# OpenPack_BATMOD_V1p0_PWR.net
KiCad netlist of a schematic drawn in Altium Designer
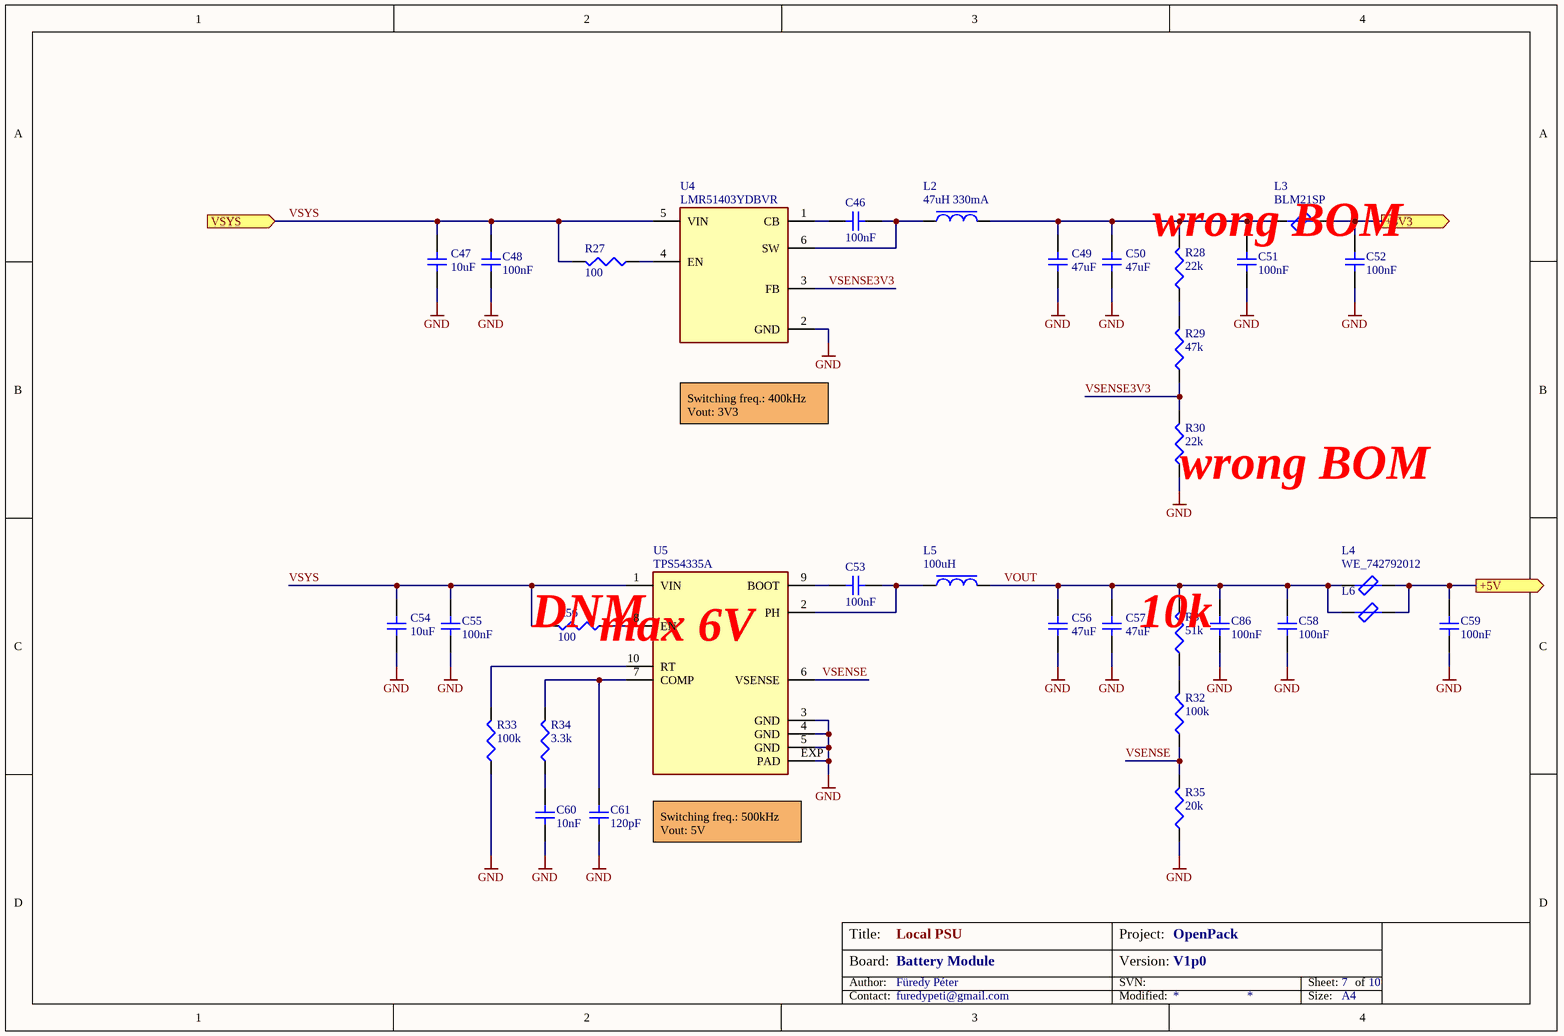
[diagram p0: OpenPack_BATMOD_V1p0_PWR.SchDoc]

(export (version "E")
  (design (tool "Eeschema 10.0.6"))
  (components
    (comp (ref "C46")
      (value "100nF")
      (footprint "CAP_0603")
      (description "MLCC capacitor")
      (libsource (lib "SCHLIB") (part "NP-CAPACITOR"))
    )
    (comp (ref "C47")
      (value "10uF")
      (footprint "CAP_1210")
      (description "UMK325BJ106KM-P")
      (fields (field (name "PART NUMBER") "810-CGA6P1X7R1N106K2"))
      (libsource (lib "SCHLIB") (part "NP-CAPACITOR"))
    )
    (comp (ref "C48")
      (value "100nF")
      (footprint "CAP_0603")
      (description "MLCC capacitor")
      (libsource (lib "SCHLIB") (part "NP-CAPACITOR"))
    )
    (comp (ref "C49")
      (value "47uF")
      (footprint "CAP_1210")
      (description "Np-Cap")
      (fields (field (name "PART NUMBER") "80-C1210C476M4P"))
      (libsource (lib "SCHLIB") (part "NP-CAPACITOR"))
    )
    (comp (ref "C50")
      (value "47uF")
      (footprint "CAP_1210")
      (description "Np-Cap")
      (fields (field (name "PART NUMBER") "80-C1210C476M4P"))
      (libsource (lib "SCHLIB") (part "NP-CAPACITOR"))
    )
    (comp (ref "C51")
      (value "100nF")
      (footprint "CAP_0603")
      (description "MLCC capacitor")
      (libsource (lib "SCHLIB") (part "NP-CAPACITOR"))
    )
    (comp (ref "C52")
      (value "100nF")
      (footprint "CAP_0603")
      (description "MLCC capacitor")
      (libsource (lib "SCHLIB") (part "NP-CAPACITOR"))
    )
    (comp (ref "C53")
      (value "100nF")
      (footprint "CAP_0603")
      (description "MLCC capacitor")
      (libsource (lib "SCHLIB") (part "NP-CAPACITOR"))
    )
    (comp (ref "C54")
      (value "10uF")
      (footprint "CAP_1210")
      (description "UMK325BJ106KM-P")
      (fields (field (name "PART NUMBER") "810-CGA6P1X7R1N106K2"))
      (libsource (lib "SCHLIB") (part "NP-CAPACITOR"))
    )
    (comp (ref "C55")
      (value "100nF")
      (footprint "CAP_0603")
      (description "MLCC capacitor")
      (libsource (lib "SCHLIB") (part "NP-CAPACITOR"))
    )
    (comp (ref "C56")
      (value "47uF")
      (footprint "CAP_1210")
      (description "Np-Cap")
      (fields (field (name "PART NUMBER") "80-C1210C476M4P"))
      (libsource (lib "SCHLIB") (part "NP-CAPACITOR"))
    )
    (comp (ref "C57")
      (value "47uF")
      (footprint "CAP_1210")
      (description "Np-Cap")
      (fields (field (name "PART NUMBER") "80-C1210C476M4P"))
      (libsource (lib "SCHLIB") (part "NP-CAPACITOR"))
    )
    (comp (ref "C58")
      (value "100nF")
      (footprint "CAP_0603")
      (description "MLCC capacitor")
      (libsource (lib "SCHLIB") (part "NP-CAPACITOR"))
    )
    (comp (ref "C59")
      (value "100nF")
      (footprint "CAP_0603")
      (description "MLCC capacitor")
      (libsource (lib "SCHLIB") (part "NP-CAPACITOR"))
    )
    (comp (ref "C60")
      (value "10nF")
      (footprint "CAP_0603")
      (description "MLCC capacitor")
      (libsource (lib "SCHLIB") (part "NP-CAPACITOR"))
    )
    (comp (ref "C61")
      (value "120pF")
      (footprint "CAP_0603")
      (description "MLCC capacitor")
      (libsource (lib "SCHLIB") (part "NP-CAPACITOR"))
    )
    (comp (ref "C86")
      (value "100nF")
      (footprint "CAP_0603")
      (description "MLCC capacitor")
      (libsource (lib "SCHLIB") (part "NP-CAPACITOR"))
    )
    (comp (ref "L2")
      (value "47uH 330mA")
      (footprint "IND_1210")
      (description "Power inductor")
      (fields (field (name "PART NUMBER") "81-LQH32PN470MN0L"))
      (libsource (lib "SCHLIB") (part "Inductance - 47uH"))
    )
    (comp (ref "L3")
      (value "BLM21SP")
      (footprint "IND-0805")
      (description "Chip Ferrite Bead, 1000R @100MHz, 1.6A")
      (fields (field (name "PART NUMBER") "81-BLM21SP102SN1D"))
      (libsource (lib "SCHLIB") (part "BLM21SP102SN1D"))
    )
    (comp (ref "L4")
      (value "WE_742792012")
      (footprint "IND-0805")
      (description "Chip Ferrite Bead, 33R @100MHz, 4A")
      (fields (field (name "PART NUMBER") "710-742792012"))
      (libsource (lib "SCHLIB") (part "WE_742792012"))
    )
    (comp (ref "L5")
      (value "100uH")
      (footprint "IND_2")
      (description "Ferrit core coil, 22uH 2.85A, 75mR")
      (fields (field (name "PART NUMBER") "994-MSS1038T-223MLC"))
      (libsource (lib "SCHLIB") (part "Inductance - 22uH"))
    )
    (comp (ref "L6")
      (value "WE_742792012")
      (footprint "IND-0805")
      (description "Chip Ferrite Bead, 33R @100MHz, 4A")
      (fields (field (name "PART NUMBER") "710-742792012"))
      (libsource (lib "SCHLIB") (part "WE_742792012"))
    )
    (comp (ref "R27")
      (value "100")
      (footprint "RES-0603")
      (description "Metal Film Resistor")
      (libsource (lib "SCHLIB") (part "RESISTOR"))
    )
    (comp (ref "R28")
      (value "22k")
      (footprint "RES-0603")
      (description "Metal Film Resistor")
      (libsource (lib "SCHLIB") (part "RESISTOR"))
    )
    (comp (ref "R29")
      (value "47k")
      (footprint "RES-0603")
      (description "Metal Film Resistor")
      (libsource (lib "SCHLIB") (part "RESISTOR"))
    )
    (comp (ref "R30")
      (value "22k")
      (footprint "RES-0603")
      (description "Metal Film Resistor")
      (libsource (lib "SCHLIB") (part "RESISTOR"))
    )
    (comp (ref "R31")
      (value "51k")
      (footprint "RES-0603")
      (description "Metal Film Resistor")
      (libsource (lib "SCHLIB") (part "RESISTOR"))
    )
    (comp (ref "R32")
      (value "100k")
      (footprint "RES-0603")
      (description "Metal Film Resistor")
      (libsource (lib "SCHLIB") (part "RESISTOR"))
    )
    (comp (ref "R33")
      (value "100k")
      (footprint "RES-0603")
      (description "Metal Film Resistor")
      (libsource (lib "SCHLIB") (part "RESISTOR"))
    )
    (comp (ref "R34")
      (value "3.3k")
      (footprint "RES-0603")
      (description "Metal Film Resistor")
      (libsource (lib "SCHLIB") (part "RESISTOR"))
    )
    (comp (ref "R35")
      (value "20k")
      (footprint "RES-0603")
      (description "Metal Film Resistor")
      (libsource (lib "SCHLIB") (part "RESISTOR"))
    )
    (comp (ref "R56")
      (value "100")
      (footprint "RES-0603")
      (description "Metal Film Resistor")
      (libsource (lib "SCHLIB") (part "RESISTOR"))
    )
    (comp (ref "U4")
      (value "LMR51403YDBVR")
      (footprint "SOT-23-6")
      (description "Switching Voltage Regulators 4.5V-to-42V 0.3A syn chronous buck conve")
      (fields (field (name "PART NUMBER") "595-LMR51403YDBVR"))
      (libsource (lib "SCHLIB") (part "LMR51403YDBVR"))
    )
    (comp (ref "U5")
      (value "TPS54335A")
      (footprint "VSON-10")
      (description "Switching Voltage Regulators 4.5Vto28VInp 3A Sync Step-Down Converter A 595-TPS54335ADRCT")
      (fields (field (name "PART NUMBER") "595-TPS54335ADRCR"))
      (libsource (lib "SCHLIB") (part "TPS54335A"))
    )
  )
  (nets
    (net (code "1") (name "/+3V3") (class "Default")
      (node (ref "C52") (pin "1") (pinfunction "1_1") (pintype "passive"))
      (node (ref "L3") (pin "2") (pinfunction "2_2") (pintype "passive"))
    )
    (net (code "2") (name "/+5V") (class "Default")
      (node (ref "C59") (pin "1") (pinfunction "1_1") (pintype "passive"))
      (node (ref "L4") (pin "2") (pinfunction "2_2") (pintype "passive"))
      (node (ref "L6") (pin "2") (pinfunction "2_2") (pintype "passive"))
    )
    (net (code "3") (name "/VOUT") (class "Default")
      (node (ref "C56") (pin "2") (pinfunction "2_2") (pintype "passive"))
      (node (ref "C57") (pin "2") (pinfunction "2_2") (pintype "passive"))
      (node (ref "C58") (pin "1") (pinfunction "1_1") (pintype "passive"))
      (node (ref "C86") (pin "1") (pinfunction "1_1") (pintype "passive"))
      (node (ref "L4") (pin "1") (pinfunction "1_1") (pintype "passive"))
      (node (ref "L5") (pin "2") (pinfunction "2_2") (pintype "passive"))
      (node (ref "L6") (pin "1") (pinfunction "1_1") (pintype "passive"))
      (node (ref "R31") (pin "2") (pintype "passive"))
    )
    (net (code "4") (name "/VSENSE") (class "Default")
      (node (ref "R32") (pin "1") (pintype "passive"))
      (node (ref "R35") (pin "2") (pintype "passive"))
      (node (ref "U5") (pin "6") (pinfunction "VSENSE_6") (pintype "passive"))
    )
    (net (code "5") (name "/VSENSE3V3") (class "Default")
      (node (ref "R29") (pin "1") (pintype "passive"))
      (node (ref "R30") (pin "2") (pintype "passive"))
      (node (ref "U4") (pin "3") (pinfunction "FB_3") (pintype "passive"))
    )
    (net (code "6") (name "/VSYS") (class "Default")
      (node (ref "C47") (pin "2") (pinfunction "2_2") (pintype "passive"))
      (node (ref "C48") (pin "1") (pinfunction "1_1") (pintype "passive"))
      (node (ref "C54") (pin "2") (pinfunction "2_2") (pintype "passive"))
      (node (ref "C55") (pin "1") (pinfunction "1_1") (pintype "passive"))
      (node (ref "R27") (pin "2") (pintype "passive"))
      (node (ref "R56") (pin "2") (pintype "passive"))
      (node (ref "U4") (pin "5") (pinfunction "VIN_5") (pintype "passive"))
      (node (ref "U5") (pin "1") (pinfunction "VIN_1") (pintype "passive"))
    )
    (net (code "7") (name "GND") (class "Default")
      (node (ref "C47") (pin "1") (pinfunction "1_1") (pintype "passive"))
      (node (ref "C48") (pin "2") (pinfunction "2_2") (pintype "passive"))
      (node (ref "C49") (pin "1") (pinfunction "1_1") (pintype "passive"))
      (node (ref "C50") (pin "1") (pinfunction "1_1") (pintype "passive"))
      (node (ref "C51") (pin "2") (pinfunction "2_2") (pintype "passive"))
      (node (ref "C52") (pin "2") (pinfunction "2_2") (pintype "passive"))
      (node (ref "C54") (pin "1") (pinfunction "1_1") (pintype "passive"))
      (node (ref "C55") (pin "2") (pinfunction "2_2") (pintype "passive"))
      (node (ref "C56") (pin "1") (pinfunction "1_1") (pintype "passive"))
      (node (ref "C57") (pin "1") (pinfunction "1_1") (pintype "passive"))
      (node (ref "C58") (pin "2") (pinfunction "2_2") (pintype "passive"))
      (node (ref "C59") (pin "2") (pinfunction "2_2") (pintype "passive"))
      (node (ref "C60") (pin "2") (pinfunction "2_2") (pintype "passive"))
      (node (ref "C61") (pin "2") (pinfunction "2_2") (pintype "passive"))
      (node (ref "C86") (pin "2") (pinfunction "2_2") (pintype "passive"))
      (node (ref "R30") (pin "1") (pintype "passive"))
      (node (ref "R33") (pin "1") (pintype "passive"))
      (node (ref "R35") (pin "1") (pintype "passive"))
      (node (ref "U4") (pin "2") (pinfunction "GND_2") (pintype "passive"))
      (node (ref "U5") (pin "3") (pinfunction "GND_3") (pintype "passive"))
      (node (ref "U5") (pin "4") (pinfunction "GND_4") (pintype "passive"))
      (node (ref "U5") (pin "5") (pinfunction "GND_5") (pintype "passive"))
      (node (ref "U5") (pin "EXP") (pinfunction "PAD_EXP") (pintype "passive"))
    )
    (net (code "8") (name "Net-(C49-Pad2)") (class "Default")
      (node (ref "C49") (pin "2") (pinfunction "2_2") (pintype "passive"))
      (node (ref "C50") (pin "2") (pinfunction "2_2") (pintype "passive"))
      (node (ref "C51") (pin "1") (pinfunction "1_1") (pintype "passive"))
      (node (ref "L2") (pin "2") (pinfunction "2_2") (pintype "passive"))
      (node (ref "L3") (pin "1") (pinfunction "1_1") (pintype "passive"))
      (node (ref "R28") (pin "2") (pintype "passive"))
    )
    (net (code "9") (name "Net-(C60-Pad1)") (class "Default")
      (node (ref "C60") (pin "1") (pinfunction "1_1") (pintype "passive"))
      (node (ref "R34") (pin "1") (pintype "passive"))
    )
    (net (code "10") (name "Net-(R28-Pad1)") (class "Default")
      (node (ref "R28") (pin "1") (pintype "passive"))
      (node (ref "R29") (pin "2") (pintype "passive"))
    )
    (net (code "11") (name "Net-(R31-Pad1)") (class "Default")
      (node (ref "R31") (pin "1") (pintype "passive"))
      (node (ref "R32") (pin "2") (pintype "passive"))
    )
    (net (code "12") (name "Net-(U4-CB)") (class "Default")
      (node (ref "C46") (pin "2") (pinfunction "2_2") (pintype "passive"))
      (node (ref "U4") (pin "1") (pinfunction "CB_1") (pintype "passive"))
    )
    (net (code "13") (name "Net-(U4-EN)") (class "Default")
      (node (ref "R27") (pin "1") (pintype "passive"))
      (node (ref "U4") (pin "4") (pinfunction "EN_4") (pintype "passive"))
    )
    (net (code "14") (name "Net-(U4-SW)") (class "Default")
      (node (ref "C46") (pin "1") (pinfunction "1_1") (pintype "passive"))
      (node (ref "L2") (pin "1") (pinfunction "1_1") (pintype "passive"))
      (node (ref "U4") (pin "6") (pinfunction "SW_6") (pintype "passive"))
    )
    (net (code "15") (name "Net-(U5-BOOT)") (class "Default")
      (node (ref "C53") (pin "2") (pinfunction "2_2") (pintype "passive"))
      (node (ref "U5") (pin "9") (pinfunction "BOOT_9") (pintype "passive"))
    )
    (net (code "16") (name "Net-(U5-COMP)") (class "Default")
      (node (ref "C61") (pin "1") (pinfunction "1_1") (pintype "passive"))
      (node (ref "R34") (pin "2") (pintype "passive"))
      (node (ref "U5") (pin "7") (pinfunction "COMP_7") (pintype "passive"))
    )
    (net (code "17") (name "Net-(U5-EN)") (class "Default")
      (node (ref "R56") (pin "1") (pintype "passive"))
      (node (ref "U5") (pin "8") (pinfunction "EN_8") (pintype "passive"))
    )
    (net (code "18") (name "Net-(U5-PH)") (class "Default")
      (node (ref "C53") (pin "1") (pinfunction "1_1") (pintype "passive"))
      (node (ref "L5") (pin "1") (pinfunction "1_1") (pintype "passive"))
      (node (ref "U5") (pin "2") (pinfunction "PH_2") (pintype "passive"))
    )
    (net (code "19") (name "Net-(U5-RT)") (class "Default")
      (node (ref "R33") (pin "2") (pintype "passive"))
      (node (ref "U5") (pin "10") (pinfunction "RT_10") (pintype "passive"))
    )
  )
)
